# fac_relay.net
KiCad netlist of a schematic drawn in EAGLE
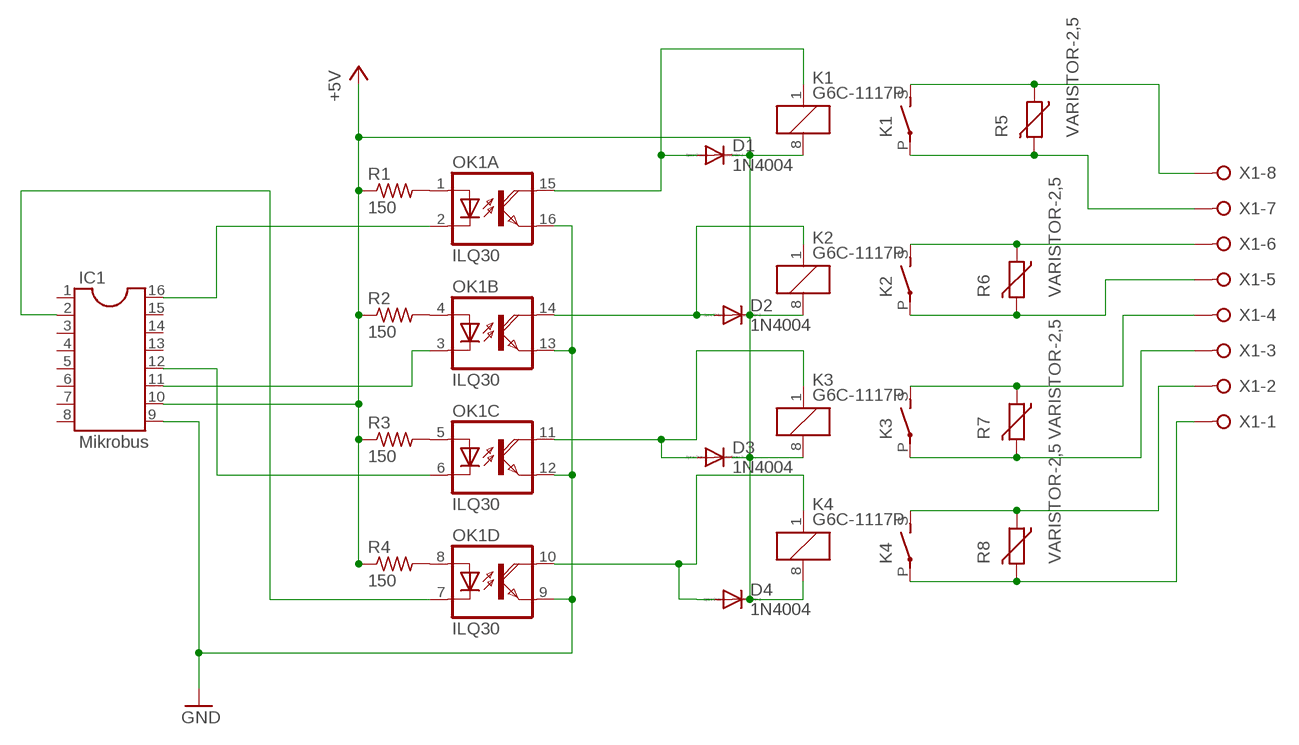
[diagram p0: schematic, sheet 1]

(export (version "E")
  (design (tool "Eeschema 10.0.6"))
  (components
    (comp (ref "D1")
      (value "1N4004")
      (footprint "eagle-import:DO41-10")
      (libsource (lib "eagle-import") (part "1N4004"))
    )
    (comp (ref "D2")
      (value "1N4004")
      (footprint "eagle-import:DO41-10")
      (libsource (lib "eagle-import") (part "1N4004"))
    )
    (comp (ref "D3")
      (value "1N4004")
      (footprint "eagle-import:DO41-10")
      (libsource (lib "eagle-import") (part "1N4004"))
    )
    (comp (ref "D4")
      (value "1N4004")
      (footprint "eagle-import:DO41-10")
      (libsource (lib "eagle-import") (part "1N4004"))
    )
    (comp (ref "IC1")
      (value "Mikrobus")
      (footprint "eagle-import:SOCKET-16")
      (libsource (lib "eagle-import") (part "DIL16S"))
    )
    (comp (ref "K1")
      (value "G6C-1117P")
      (footprint "eagle-import:G6C-1117P")
      (libsource (lib "eagle-import") (part "G6C-1117P"))
    )
    (comp (ref "K2")
      (value "G6C-1117P")
      (footprint "eagle-import:G6C-1117P")
      (libsource (lib "eagle-import") (part "G6C-1117P"))
    )
    (comp (ref "K3")
      (value "G6C-1117P")
      (footprint "eagle-import:G6C-1117P")
      (libsource (lib "eagle-import") (part "G6C-1117P"))
    )
    (comp (ref "K4")
      (value "G6C-1117P")
      (footprint "eagle-import:G6C-1117P")
      (libsource (lib "eagle-import") (part "G6C-1117P"))
    )
    (comp (ref "OK1")
      (value "ILQ30")
      (footprint "eagle-import:DIL16")
      (fields (field (name "MF") "VISHAY/TELEFUNKEN"))
      (libsource (lib "eagle-import") (part "ILQ30"))
    )
    (comp (ref "R1")
      (value "150")
      (footprint "eagle-import:0204_5")
      (libsource (lib "eagle-import") (part "R-US_0204/5"))
    )
    (comp (ref "R2")
      (value "150")
      (footprint "eagle-import:0204_5")
      (libsource (lib "eagle-import") (part "R-US_0204/5"))
    )
    (comp (ref "R3")
      (value "150")
      (footprint "eagle-import:0204_5")
      (libsource (lib "eagle-import") (part "R-US_0204/5"))
    )
    (comp (ref "R4")
      (value "150")
      (footprint "eagle-import:0204_5")
      (libsource (lib "eagle-import") (part "R-US_0204/5"))
    )
    (comp (ref "R5")
      (value "VARISTOR-2,5")
      (footprint "eagle-import:R-5")
      (libsource (lib "eagle-import") (part "VARISTOR-2,5"))
    )
    (comp (ref "R6")
      (value "VARISTOR-2,5")
      (footprint "eagle-import:R-5")
      (libsource (lib "eagle-import") (part "VARISTOR-2,5"))
    )
    (comp (ref "R7")
      (value "VARISTOR-2,5")
      (footprint "eagle-import:R-5")
      (libsource (lib "eagle-import") (part "VARISTOR-2,5"))
    )
    (comp (ref "R8")
      (value "VARISTOR-2,5")
      (footprint "eagle-import:R-5")
      (libsource (lib "eagle-import") (part "VARISTOR-2,5"))
    )
    (comp (ref "X1")
      (value "W237-08P")
      (footprint "eagle-import:W237-8P")
      (libsource (lib "eagle-import") (part "W237-08P"))
    )
  )
  (nets
    (net (code "1") (name "+5V") (class "Default")
      (node (ref "D1") (pin "C") (pinfunction "C_C") (pintype "passive"))
      (node (ref "D2") (pin "C") (pinfunction "C_C") (pintype "passive"))
      (node (ref "D3") (pin "C") (pinfunction "C_C") (pintype "passive"))
      (node (ref "D4") (pin "C") (pinfunction "C_C") (pintype "passive"))
      (node (ref "IC1") (pin "10") (pinfunction "10_10") (pintype "passive"))
      (node (ref "K1") (pin "8") (pinfunction "2_8") (pintype "passive"))
      (node (ref "K2") (pin "8") (pinfunction "2_8") (pintype "passive"))
      (node (ref "K3") (pin "8") (pinfunction "2_8") (pintype "passive"))
      (node (ref "K4") (pin "8") (pinfunction "2_8") (pintype "passive"))
      (node (ref "R1") (pin "1") (pinfunction "1_1") (pintype "passive"))
      (node (ref "R2") (pin "1") (pinfunction "1_1") (pintype "passive"))
      (node (ref "R3") (pin "1") (pinfunction "1_1") (pintype "passive"))
      (node (ref "R4") (pin "1") (pinfunction "1_1") (pintype "passive"))
    )
    (net (code "2") (name "GND") (class "Default")
      (node (ref "IC1") (pin "9") (pinfunction "9_9") (pintype "passive"))
      (node (ref "OK1") (pin "12") (pinfunction "EMI_12") (pintype "passive"))
      (node (ref "OK1") (pin "13") (pinfunction "EMI_13") (pintype "passive"))
      (node (ref "OK1") (pin "16") (pinfunction "EMI_16") (pintype "passive"))
      (node (ref "OK1") (pin "9") (pinfunction "EMI_9") (pintype "passive"))
    )
    (net (code "3") (name "Net-(OK1A-A)") (class "Default")
      (node (ref "OK1") (pin "1") (pinfunction "A_1") (pintype "passive"))
      (node (ref "R1") (pin "2") (pinfunction "2_2") (pintype "passive"))
    )
    (net (code "4") (name "Net-(OK1A-C)") (class "Default")
      (node (ref "IC1") (pin "16") (pinfunction "16_16") (pintype "passive"))
      (node (ref "OK1") (pin "2") (pinfunction "C_2") (pintype "passive"))
    )
    (net (code "5") (name "Net-(OK1A-COL)") (class "Default")
      (node (ref "D1") (pin "A") (pinfunction "A_A") (pintype "passive"))
      (node (ref "K1") (pin "1") (pinfunction "1_1") (pintype "passive"))
      (node (ref "OK1") (pin "15") (pinfunction "COL_15") (pintype "passive"))
    )
    (net (code "6") (name "Net-(OK1B-A)") (class "Default")
      (node (ref "OK1") (pin "4") (pinfunction "A_4") (pintype "passive"))
      (node (ref "R2") (pin "2") (pinfunction "2_2") (pintype "passive"))
    )
    (net (code "7") (name "Net-(OK1B-C)") (class "Default")
      (node (ref "IC1") (pin "11") (pinfunction "11_11") (pintype "passive"))
      (node (ref "OK1") (pin "3") (pinfunction "C_3") (pintype "passive"))
    )
    (net (code "8") (name "Net-(OK1B-COL)") (class "Default")
      (node (ref "D2") (pin "A") (pinfunction "A_A") (pintype "passive"))
      (node (ref "K2") (pin "1") (pinfunction "1_1") (pintype "passive"))
      (node (ref "OK1") (pin "14") (pinfunction "COL_14") (pintype "passive"))
    )
    (net (code "9") (name "Net-(OK1C-A)") (class "Default")
      (node (ref "OK1") (pin "5") (pinfunction "A_5") (pintype "passive"))
      (node (ref "R3") (pin "2") (pinfunction "2_2") (pintype "passive"))
    )
    (net (code "10") (name "Net-(OK1C-C)") (class "Default")
      (node (ref "IC1") (pin "12") (pinfunction "12_12") (pintype "passive"))
      (node (ref "OK1") (pin "6") (pinfunction "C_6") (pintype "passive"))
    )
    (net (code "11") (name "Net-(OK1C-COL)") (class "Default")
      (node (ref "D3") (pin "A") (pinfunction "A_A") (pintype "passive"))
      (node (ref "K3") (pin "1") (pinfunction "1_1") (pintype "passive"))
      (node (ref "OK1") (pin "11") (pinfunction "COL_11") (pintype "passive"))
    )
    (net (code "12") (name "Net-(OK1D-A)") (class "Default")
      (node (ref "OK1") (pin "8") (pinfunction "A_8") (pintype "passive"))
      (node (ref "R4") (pin "2") (pinfunction "2_2") (pintype "passive"))
    )
    (net (code "13") (name "Net-(OK1D-C)") (class "Default")
      (node (ref "IC1") (pin "2") (pinfunction "2_2") (pintype "passive"))
      (node (ref "OK1") (pin "7") (pinfunction "C_7") (pintype "passive"))
    )
    (net (code "14") (name "Net-(OK1D-COL)") (class "Default")
      (node (ref "D4") (pin "A") (pinfunction "A_A") (pintype "passive"))
      (node (ref "K4") (pin "1") (pinfunction "1_1") (pintype "passive"))
      (node (ref "OK1") (pin "10") (pinfunction "COL_10") (pintype "passive"))
    )
    (net (code "15") (name "Net-(X1A-KL)") (class "Default")
      (node (ref "K4") (pin "P") (pinfunction "P_P") (pintype "passive"))
      (node (ref "R8") (pin "2") (pinfunction "2_2") (pintype "passive"))
      (node (ref "X1") (pin "1") (pinfunction "KL_1") (pintype "passive"))
    )
    (net (code "16") (name "Net-(X1B-KL)") (class "Default")
      (node (ref "K4") (pin "S") (pinfunction "S_S") (pintype "passive"))
      (node (ref "R8") (pin "1") (pinfunction "1_1") (pintype "passive"))
      (node (ref "X1") (pin "2") (pinfunction "KL_2") (pintype "passive"))
    )
    (net (code "17") (name "Net-(X1C-KL)") (class "Default")
      (node (ref "K3") (pin "P") (pinfunction "P_P") (pintype "passive"))
      (node (ref "R7") (pin "2") (pinfunction "2_2") (pintype "passive"))
      (node (ref "X1") (pin "3") (pinfunction "KL_3") (pintype "passive"))
    )
    (net (code "18") (name "Net-(X1D-KL)") (class "Default")
      (node (ref "K3") (pin "S") (pinfunction "S_S") (pintype "passive"))
      (node (ref "R7") (pin "1") (pinfunction "1_1") (pintype "passive"))
      (node (ref "X1") (pin "4") (pinfunction "KL_4") (pintype "passive"))
    )
    (net (code "19") (name "Net-(X1E-KL)") (class "Default")
      (node (ref "K2") (pin "P") (pinfunction "P_P") (pintype "passive"))
      (node (ref "R6") (pin "2") (pinfunction "2_2") (pintype "passive"))
      (node (ref "X1") (pin "5") (pinfunction "KL_5") (pintype "passive"))
    )
    (net (code "20") (name "Net-(X1F-KL)") (class "Default")
      (node (ref "K2") (pin "S") (pinfunction "S_S") (pintype "passive"))
      (node (ref "R6") (pin "1") (pinfunction "1_1") (pintype "passive"))
      (node (ref "X1") (pin "6") (pinfunction "KL_6") (pintype "passive"))
    )
    (net (code "21") (name "Net-(X1G-KL)") (class "Default")
      (node (ref "K1") (pin "P") (pinfunction "P_P") (pintype "passive"))
      (node (ref "R5") (pin "2") (pinfunction "2_2") (pintype "passive"))
      (node (ref "X1") (pin "7") (pinfunction "KL_7") (pintype "passive"))
    )
    (net (code "22") (name "Net-(X1H-KL)") (class "Default")
      (node (ref "K1") (pin "S") (pinfunction "S_S") (pintype "passive"))
      (node (ref "R5") (pin "1") (pinfunction "1_1") (pintype "passive"))
      (node (ref "X1") (pin "8") (pinfunction "KL_8") (pintype "passive"))
    )
    (net (code "23") (name "unconnected-(IC1-Pad1)") (class "Default")
      (node (ref "IC1") (pin "1") (pinfunction "1_1") (pintype "passive"))
    )
    (net (code "24") (name "unconnected-(IC1-Pad3)") (class "Default")
      (node (ref "IC1") (pin "3") (pinfunction "3_3") (pintype "passive"))
    )
    (net (code "25") (name "unconnected-(IC1-Pad4)") (class "Default")
      (node (ref "IC1") (pin "4") (pinfunction "4_4") (pintype "passive"))
    )
    (net (code "26") (name "unconnected-(IC1-Pad5)") (class "Default")
      (node (ref "IC1") (pin "5") (pinfunction "5_5") (pintype "passive"))
    )
    (net (code "27") (name "unconnected-(IC1-Pad6)") (class "Default")
      (node (ref "IC1") (pin "6") (pinfunction "6_6") (pintype "passive"))
    )
    (net (code "28") (name "unconnected-(IC1-Pad7)") (class "Default")
      (node (ref "IC1") (pin "7") (pinfunction "7_7") (pintype "passive"))
    )
    (net (code "29") (name "unconnected-(IC1-Pad8)") (class "Default")
      (node (ref "IC1") (pin "8") (pinfunction "8_8") (pintype "passive"))
    )
    (net (code "30") (name "unconnected-(IC1-Pad13)") (class "Default")
      (node (ref "IC1") (pin "13") (pinfunction "13_13") (pintype "passive"))
    )
    (net (code "31") (name "unconnected-(IC1-Pad14)") (class "Default")
      (node (ref "IC1") (pin "14") (pinfunction "14_14") (pintype "passive"))
    )
    (net (code "32") (name "unconnected-(IC1-Pad15)") (class "Default")
      (node (ref "IC1") (pin "15") (pinfunction "15_15") (pintype "passive"))
    )
  )
)
